# S0-energy-meter-v1_1.net
KiCad netlist of a schematic drawn in EAGLE
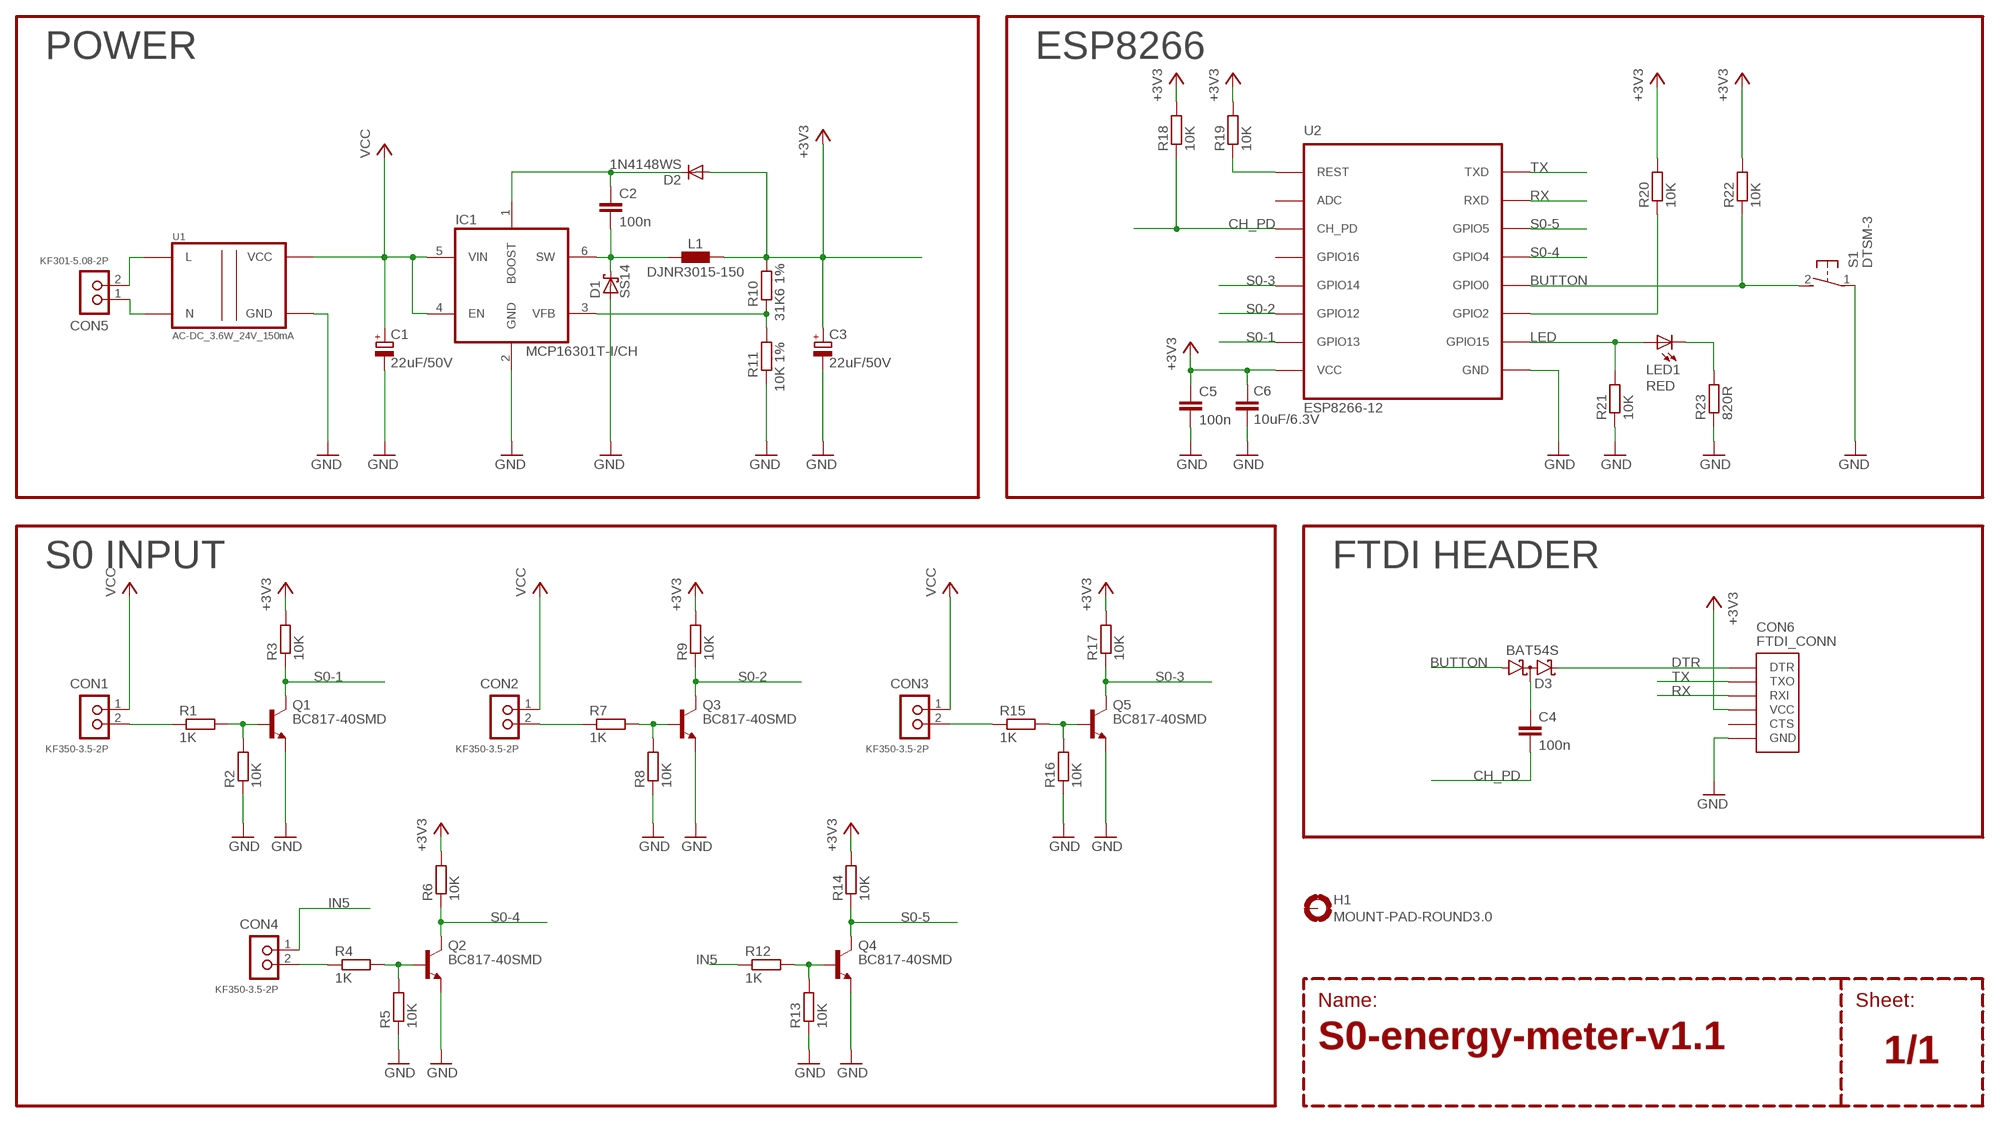
[diagram p0: schematic, sheet 1]

(export (version "E")
  (design (tool "Eeschema 10.0.6"))
  (components
    (comp (ref "C1")
      (value "22uF/50V")
      (footprint "eagle-import:PANASONIC_C")
      (libsource (lib "eagle-import") (part "CPOL-EUC"))
    )
    (comp (ref "C2")
      (value "100n")
      (footprint "eagle-import:C0805")
      (libsource (lib "eagle-import") (part "rcl_334_C-EUC0805"))
    )
    (comp (ref "C3")
      (value "22uF/50V")
      (footprint "eagle-import:PANASONIC_C")
      (libsource (lib "eagle-import") (part "CPOL-EUC"))
    )
    (comp (ref "C4")
      (value "100n")
      (footprint "eagle-import:C0805")
      (libsource (lib "eagle-import") (part "C-EUC0805"))
    )
    (comp (ref "C5")
      (value "100n")
      (footprint "eagle-import:C0805")
      (libsource (lib "eagle-import") (part "rcl_334_C-EUC0805"))
    )
    (comp (ref "C6")
      (value "10uF/6.3V")
      (footprint "eagle-import:C0805")
      (libsource (lib "eagle-import") (part "rcl_334_C-EUC0805"))
    )
    (comp (ref "CON1")
      (value "KF350-3.5-2P")
      (footprint "eagle-import:KF350-3.50-2P")
      (libsource (lib "eagle-import") (part "KF350-3.5-2P"))
    )
    (comp (ref "CON2")
      (value "KF350-3.5-2P")
      (footprint "eagle-import:KF350-3.50-2P")
      (libsource (lib "eagle-import") (part "KF350-3.5-2P"))
    )
    (comp (ref "CON3")
      (value "KF350-3.5-2P")
      (footprint "eagle-import:KF350-3.50-2P")
      (libsource (lib "eagle-import") (part "KF350-3.5-2P"))
    )
    (comp (ref "CON4")
      (value "KF350-3.5-2P")
      (footprint "eagle-import:KF350-3.50-2P")
      (libsource (lib "eagle-import") (part "KF350-3.5-2P"))
    )
    (comp (ref "CON5")
      (value "KF301-5.08-2P")
      (footprint "eagle-import:KF301-5.08-2P")
      (libsource (lib "eagle-import") (part "KF301-?-2P5.08"))
    )
    (comp (ref "CON6")
      (value "FTDI_CONN")
      (footprint "eagle-import:FTDI")
      (libsource (lib "eagle-import") (part "FTDI_CONN"))
    )
    (comp (ref "D1")
      (value "SS14")
      (footprint "eagle-import:DO214AC")
      (libsource (lib "eagle-import") (part "SS?14"))
    )
    (comp (ref "D2")
      (value "1N4148WS")
      (footprint "eagle-import:SOD323")
      (libsource (lib "eagle-import") (part "1N4148WS"))
    )
    (comp (ref "D3")
      (value "BAT54S")
      (footprint "eagle-import:SOT23")
      (libsource (lib "eagle-import") (part "BAT54S"))
    )
    (comp (ref "H1")
      (value "MOUNT-PAD-ROUND3.0")
      (footprint "eagle-import:3,0-PAD")
      (libsource (lib "eagle-import") (part "MOUNT-PAD-ROUND3.0"))
    )
    (comp (ref "IC1")
      (value "MCP16301T-I/CH")
      (footprint "eagle-import:SOT23-6")
      (libsource (lib "eagle-import") (part "MCP16301T-I/?CH"))
    )
    (comp (ref "L1")
      (value "DJNR3015-150")
      (footprint "eagle-import:L3015")
      (libsource (lib "eagle-import") (part "DJNR?-3015150"))
    )
    (comp (ref "LED1")
      (value "RED")
      (footprint "eagle-import:LED0805")
      (libsource (lib "eagle-import") (part "LED0805"))
    )
    (comp (ref "Q1")
      (value "BC817-40SMD")
      (footprint "eagle-import:SOT23-BEC")
      (libsource (lib "eagle-import") (part "BC817SMD-40"))
    )
    (comp (ref "Q2")
      (value "BC817-40SMD")
      (footprint "eagle-import:SOT23-BEC")
      (libsource (lib "eagle-import") (part "BC817SMD-40"))
    )
    (comp (ref "Q3")
      (value "BC817-40SMD")
      (footprint "eagle-import:SOT23-BEC")
      (libsource (lib "eagle-import") (part "BC817SMD-40"))
    )
    (comp (ref "Q4")
      (value "BC817-40SMD")
      (footprint "eagle-import:SOT23-BEC")
      (libsource (lib "eagle-import") (part "BC817SMD-40"))
    )
    (comp (ref "Q5")
      (value "BC817-40SMD")
      (footprint "eagle-import:SOT23-BEC")
      (libsource (lib "eagle-import") (part "BC817SMD-40"))
    )
    (comp (ref "R1")
      (value "1K")
      (footprint "eagle-import:R0805")
      (libsource (lib "eagle-import") (part "R-EU_R0805"))
    )
    (comp (ref "R2")
      (value "10K")
      (footprint "eagle-import:R0805")
      (libsource (lib "eagle-import") (part "R-EU_R0805"))
    )
    (comp (ref "R3")
      (value "10K")
      (footprint "eagle-import:R0805")
      (libsource (lib "eagle-import") (part "R-EU_R0805"))
    )
    (comp (ref "R4")
      (value "1K")
      (footprint "eagle-import:R0805")
      (libsource (lib "eagle-import") (part "R-EU_R0805"))
    )
    (comp (ref "R5")
      (value "10K")
      (footprint "eagle-import:R0805")
      (libsource (lib "eagle-import") (part "R-EU_R0805"))
    )
    (comp (ref "R6")
      (value "10K")
      (footprint "eagle-import:R0805")
      (libsource (lib "eagle-import") (part "R-EU_R0805"))
    )
    (comp (ref "R7")
      (value "1K")
      (footprint "eagle-import:R0805")
      (libsource (lib "eagle-import") (part "R-EU_R0805"))
    )
    (comp (ref "R8")
      (value "10K")
      (footprint "eagle-import:R0805")
      (libsource (lib "eagle-import") (part "R-EU_R0805"))
    )
    (comp (ref "R9")
      (value "10K")
      (footprint "eagle-import:R0805")
      (libsource (lib "eagle-import") (part "R-EU_R0805"))
    )
    (comp (ref "R10")
      (value "31K6 1%")
      (footprint "eagle-import:R0805")
      (libsource (lib "eagle-import") (part "R-EU_R0805"))
    )
    (comp (ref "R11")
      (value "10K 1%")
      (footprint "eagle-import:R0805")
      (libsource (lib "eagle-import") (part "R-EU_R0805"))
    )
    (comp (ref "R12")
      (value "1K")
      (footprint "eagle-import:R0805")
      (libsource (lib "eagle-import") (part "R-EU_R0805"))
    )
    (comp (ref "R13")
      (value "10K")
      (footprint "eagle-import:R0805")
      (libsource (lib "eagle-import") (part "R-EU_R0805"))
    )
    (comp (ref "R14")
      (value "10K")
      (footprint "eagle-import:R0805")
      (libsource (lib "eagle-import") (part "R-EU_R0805"))
    )
    (comp (ref "R15")
      (value "1K")
      (footprint "eagle-import:R0805")
      (libsource (lib "eagle-import") (part "R-EU_R0805"))
    )
    (comp (ref "R16")
      (value "10K")
      (footprint "eagle-import:R0805")
      (libsource (lib "eagle-import") (part "R-EU_R0805"))
    )
    (comp (ref "R17")
      (value "10K")
      (footprint "eagle-import:R0805")
      (libsource (lib "eagle-import") (part "R-EU_R0805"))
    )
    (comp (ref "R18")
      (value "10K")
      (footprint "eagle-import:R0805")
      (libsource (lib "eagle-import") (part "R-EU_R0805"))
    )
    (comp (ref "R19")
      (value "10K")
      (footprint "eagle-import:R0805")
      (libsource (lib "eagle-import") (part "R-EU_R0805"))
    )
    (comp (ref "R20")
      (value "10K")
      (footprint "eagle-import:R0805")
      (libsource (lib "eagle-import") (part "R-EU_R0805"))
    )
    (comp (ref "R21")
      (value "10K")
      (footprint "eagle-import:R0805")
      (libsource (lib "eagle-import") (part "R-EU_R0805"))
    )
    (comp (ref "R22")
      (value "10K")
      (footprint "eagle-import:R0805")
      (libsource (lib "eagle-import") (part "R-EU_R0805"))
    )
    (comp (ref "R23")
      (value "820R")
      (footprint "eagle-import:R0805")
      (libsource (lib "eagle-import") (part "R-EU_R0805"))
    )
    (comp (ref "S1")
      (value "DTSM-3")
      (footprint "eagle-import:DTSM-3")
      (libsource (lib "eagle-import") (part "DTSM-3"))
    )
    (comp (ref "U1")
      (value "AC-DC_3.6W_24V_150mA")
      (footprint "eagle-import:AC_DC_24V_150MA")
      (libsource (lib "eagle-import") (part "AC-DC_?3.6W"))
    )
    (comp (ref "U2")
      (value "ESP8266-12")
      (footprint "eagle-import:ESP-12")
      (libsource (lib "eagle-import") (part "ESP8266-12"))
    )
  )
  (nets
    (net (code "1") (name "+3V3") (class "Default")
      (node (ref "C3") (pin "+") (pinfunction "+_+") (pintype "passive"))
      (node (ref "C5") (pin "1") (pinfunction "1_1") (pintype "passive"))
      (node (ref "C6") (pin "1") (pinfunction "1_1") (pintype "passive"))
      (node (ref "CON6") (pin "P$4") (pinfunction "VCC_P$4") (pintype "bidirectional"))
      (node (ref "D2") (pin "A") (pinfunction "A_A") (pintype "passive"))
      (node (ref "L1") (pin "1") (pinfunction "1_1") (pintype "passive"))
      (node (ref "R10") (pin "2") (pinfunction "2_2") (pintype "passive"))
      (node (ref "R14") (pin "2") (pinfunction "2_2") (pintype "passive"))
      (node (ref "R17") (pin "2") (pinfunction "2_2") (pintype "passive"))
      (node (ref "R18") (pin "2") (pinfunction "2_2") (pintype "passive"))
      (node (ref "R19") (pin "2") (pinfunction "2_2") (pintype "passive"))
      (node (ref "R20") (pin "2") (pinfunction "2_2") (pintype "passive"))
      (node (ref "R22") (pin "2") (pinfunction "2_2") (pintype "passive"))
      (node (ref "R3") (pin "2") (pinfunction "2_2") (pintype "passive"))
      (node (ref "R6") (pin "2") (pinfunction "2_2") (pintype "passive"))
      (node (ref "R9") (pin "2") (pinfunction "2_2") (pintype "passive"))
      (node (ref "U2") (pin "VCC") (pinfunction "VCC_VCC") (pintype "power_in"))
    )
    (net (code "2") (name "/BUTTON") (class "Default")
      (node (ref "D3") (pin "1") (pinfunction "A1_1") (pintype "passive"))
      (node (ref "R22") (pin "1") (pinfunction "1_1") (pintype "passive"))
      (node (ref "S1") (pin "2") (pinfunction "2_2") (pintype "passive"))
      (node (ref "U2") (pin "GPIO0") (pinfunction "GPIO0_GPIO0") (pintype "bidirectional"))
    )
    (net (code "3") (name "/CH_PD") (class "Default")
      (node (ref "C4") (pin "2") (pinfunction "2_2") (pintype "passive"))
      (node (ref "R18") (pin "1") (pinfunction "1_1") (pintype "passive"))
      (node (ref "U2") (pin "CH_PD") (pinfunction "CH_PD_CH_PD") (pintype "power_in"))
    )
    (net (code "4") (name "/DTR") (class "Default")
      (node (ref "CON6") (pin "P$1") (pinfunction "DTR_P$1") (pintype "bidirectional"))
      (node (ref "D3") (pin "2") (pinfunction "C2_2") (pintype "passive"))
    )
    (net (code "5") (name "/IN5") (class "Default")
      (node (ref "CON4") (pin "1") (pinfunction "1_1") (pintype "passive"))
      (node (ref "R12") (pin "1") (pinfunction "1_1") (pintype "passive"))
    )
    (net (code "6") (name "/LED") (class "Default")
      (node (ref "LED1") (pin "A") (pinfunction "A_A") (pintype "passive"))
      (node (ref "R21") (pin "2") (pinfunction "2_2") (pintype "passive"))
      (node (ref "U2") (pin "GPIO15") (pinfunction "GPIO15_GPIO15") (pintype "bidirectional"))
    )
    (net (code "7") (name "/RX") (class "Default")
      (node (ref "CON6") (pin "P$3") (pinfunction "RXI_P$3") (pintype "bidirectional"))
      (node (ref "U2") (pin "RXD") (pinfunction "RXD_RXD") (pintype "bidirectional"))
    )
    (net (code "8") (name "/S0-1") (class "Default")
      (node (ref "Q1") (pin "C") (pinfunction "C_C") (pintype "passive"))
      (node (ref "R3") (pin "1") (pinfunction "1_1") (pintype "passive"))
      (node (ref "U2") (pin "GPIO13") (pinfunction "GPIO13_GPIO13") (pintype "bidirectional"))
    )
    (net (code "9") (name "/S0-2") (class "Default")
      (node (ref "Q3") (pin "C") (pinfunction "C_C") (pintype "passive"))
      (node (ref "R9") (pin "1") (pinfunction "1_1") (pintype "passive"))
      (node (ref "U2") (pin "GPIO12") (pinfunction "GPIO12_GPIO12") (pintype "bidirectional"))
    )
    (net (code "10") (name "/S0-3") (class "Default")
      (node (ref "Q5") (pin "C") (pinfunction "C_C") (pintype "passive"))
      (node (ref "R17") (pin "1") (pinfunction "1_1") (pintype "passive"))
      (node (ref "U2") (pin "GPIO14") (pinfunction "GPIO14_GPIO14") (pintype "bidirectional"))
    )
    (net (code "11") (name "/S0-4") (class "Default")
      (node (ref "Q2") (pin "C") (pinfunction "C_C") (pintype "passive"))
      (node (ref "R6") (pin "1") (pinfunction "1_1") (pintype "passive"))
      (node (ref "U2") (pin "GPIO4") (pinfunction "GPIO4_GPIO4") (pintype "bidirectional"))
    )
    (net (code "12") (name "/S0-5") (class "Default")
      (node (ref "Q4") (pin "C") (pinfunction "C_C") (pintype "passive"))
      (node (ref "R14") (pin "1") (pinfunction "1_1") (pintype "passive"))
      (node (ref "U2") (pin "GPIO5") (pinfunction "GPIO5_GPIO5") (pintype "bidirectional"))
    )
    (net (code "13") (name "/TX") (class "Default")
      (node (ref "CON6") (pin "P$2") (pinfunction "TXO_P$2") (pintype "bidirectional"))
      (node (ref "U2") (pin "TXD") (pinfunction "TXD_TXD") (pintype "bidirectional"))
    )
    (net (code "14") (name "GND") (class "Default")
      (node (ref "C1") (pin "-") (pinfunction "-_-") (pintype "passive"))
      (node (ref "C3") (pin "-") (pinfunction "-_-") (pintype "passive"))
      (node (ref "C5") (pin "2") (pinfunction "2_2") (pintype "passive"))
      (node (ref "C6") (pin "2") (pinfunction "2_2") (pintype "passive"))
      (node (ref "CON6") (pin "P$6") (pinfunction "GND_P$6") (pintype "bidirectional"))
      (node (ref "D1") (pin "A") (pinfunction "A_A") (pintype "passive"))
      (node (ref "IC1") (pin "2") (pinfunction "GND_2") (pintype "power_in"))
      (node (ref "Q1") (pin "E") (pinfunction "E_E") (pintype "passive"))
      (node (ref "Q2") (pin "E") (pinfunction "E_E") (pintype "passive"))
      (node (ref "Q3") (pin "E") (pinfunction "E_E") (pintype "passive"))
      (node (ref "Q4") (pin "E") (pinfunction "E_E") (pintype "passive"))
      (node (ref "Q5") (pin "E") (pinfunction "E_E") (pintype "passive"))
      (node (ref "R11") (pin "1") (pinfunction "1_1") (pintype "passive"))
      (node (ref "R13") (pin "1") (pinfunction "1_1") (pintype "passive"))
      (node (ref "R16") (pin "1") (pinfunction "1_1") (pintype "passive"))
      (node (ref "R2") (pin "1") (pinfunction "1_1") (pintype "passive"))
      (node (ref "R21") (pin "1") (pinfunction "1_1") (pintype "passive"))
      (node (ref "R23") (pin "1") (pinfunction "1_1") (pintype "passive"))
      (node (ref "R5") (pin "1") (pinfunction "1_1") (pintype "passive"))
      (node (ref "R8") (pin "1") (pinfunction "1_1") (pintype "passive"))
      (node (ref "S1") (pin "1") (pinfunction "1_1") (pintype "passive"))
      (node (ref "U1") (pin "GND") (pinfunction "GND_GND") (pintype "power_in"))
      (node (ref "U2") (pin "GND") (pinfunction "GND_GND") (pintype "power_in"))
    )
    (net (code "15") (name "Net-(CON1-Pad2)") (class "Default")
      (node (ref "CON1") (pin "2") (pinfunction "2_2") (pintype "passive"))
      (node (ref "R1") (pin "1") (pinfunction "1_1") (pintype "passive"))
    )
    (net (code "16") (name "Net-(CON2-Pad2)") (class "Default")
      (node (ref "CON2") (pin "2") (pinfunction "2_2") (pintype "passive"))
      (node (ref "R7") (pin "1") (pinfunction "1_1") (pintype "passive"))
    )
    (net (code "17") (name "Net-(CON3-Pad2)") (class "Default")
      (node (ref "CON3") (pin "2") (pinfunction "2_2") (pintype "passive"))
      (node (ref "R15") (pin "1") (pinfunction "1_1") (pintype "passive"))
    )
    (net (code "18") (name "Net-(CON4-Pad2)") (class "Default")
      (node (ref "CON4") (pin "2") (pinfunction "2_2") (pintype "passive"))
      (node (ref "R4") (pin "1") (pinfunction "1_1") (pintype "passive"))
    )
    (net (code "19") (name "Net-(CON5-Pad1)") (class "Default")
      (node (ref "CON5") (pin "1") (pinfunction "1_1") (pintype "passive"))
      (node (ref "U1") (pin "N") (pinfunction "N_N") (pintype "power_in"))
    )
    (net (code "20") (name "Net-(CON5-Pad2)") (class "Default")
      (node (ref "CON5") (pin "2") (pinfunction "2_2") (pintype "passive"))
      (node (ref "U1") (pin "L") (pinfunction "L_L") (pintype "power_in"))
    )
    (net (code "21") (name "Net-(D3-C1A2)") (class "Default")
      (node (ref "C4") (pin "1") (pinfunction "1_1") (pintype "passive"))
      (node (ref "D3") (pin "3") (pinfunction "C1A2_3") (pintype "passive"))
    )
    (net (code "22") (name "Net-(IC1-BOOST)") (class "Default")
      (node (ref "C2") (pin "1") (pinfunction "1_1") (pintype "passive"))
      (node (ref "D2") (pin "C") (pinfunction "C_C") (pintype "passive"))
      (node (ref "IC1") (pin "1") (pinfunction "BOOST_1") (pintype "passive"))
    )
    (net (code "23") (name "Net-(IC1-SW)") (class "Default")
      (node (ref "C2") (pin "2") (pinfunction "2_2") (pintype "passive"))
      (node (ref "D1") (pin "C") (pinfunction "C_C") (pintype "passive"))
      (node (ref "IC1") (pin "6") (pinfunction "SW_6") (pintype "output"))
      (node (ref "L1") (pin "2") (pinfunction "2_2") (pintype "passive"))
    )
    (net (code "24") (name "Net-(IC1-VFB)") (class "Default")
      (node (ref "IC1") (pin "3") (pinfunction "VFB_3") (pintype "input"))
      (node (ref "R10") (pin "1") (pinfunction "1_1") (pintype "passive"))
      (node (ref "R11") (pin "2") (pinfunction "2_2") (pintype "passive"))
    )
    (net (code "25") (name "Net-(LED1-PadC)") (class "Default")
      (node (ref "LED1") (pin "C") (pinfunction "C_C") (pintype "passive"))
      (node (ref "R23") (pin "2") (pinfunction "2_2") (pintype "passive"))
    )
    (net (code "26") (name "Net-(Q1-PadB)") (class "Default")
      (node (ref "Q1") (pin "B") (pinfunction "B_B") (pintype "passive"))
      (node (ref "R1") (pin "2") (pinfunction "2_2") (pintype "passive"))
      (node (ref "R2") (pin "2") (pinfunction "2_2") (pintype "passive"))
    )
    (net (code "27") (name "Net-(Q2-PadB)") (class "Default")
      (node (ref "Q2") (pin "B") (pinfunction "B_B") (pintype "passive"))
      (node (ref "R4") (pin "2") (pinfunction "2_2") (pintype "passive"))
      (node (ref "R5") (pin "2") (pinfunction "2_2") (pintype "passive"))
    )
    (net (code "28") (name "Net-(Q3-PadB)") (class "Default")
      (node (ref "Q3") (pin "B") (pinfunction "B_B") (pintype "passive"))
      (node (ref "R7") (pin "2") (pinfunction "2_2") (pintype "passive"))
      (node (ref "R8") (pin "2") (pinfunction "2_2") (pintype "passive"))
    )
    (net (code "29") (name "Net-(Q4-PadB)") (class "Default")
      (node (ref "Q4") (pin "B") (pinfunction "B_B") (pintype "passive"))
      (node (ref "R12") (pin "2") (pinfunction "2_2") (pintype "passive"))
      (node (ref "R13") (pin "2") (pinfunction "2_2") (pintype "passive"))
    )
    (net (code "30") (name "Net-(Q5-PadB)") (class "Default")
      (node (ref "Q5") (pin "B") (pinfunction "B_B") (pintype "passive"))
      (node (ref "R15") (pin "2") (pinfunction "2_2") (pintype "passive"))
      (node (ref "R16") (pin "2") (pinfunction "2_2") (pintype "passive"))
    )
    (net (code "31") (name "Net-(R19-Pad1)") (class "Default")
      (node (ref "R19") (pin "1") (pinfunction "1_1") (pintype "passive"))
      (node (ref "U2") (pin "REST") (pinfunction "REST_REST") (pintype "bidirectional"))
    )
    (net (code "32") (name "Net-(R20-Pad1)") (class "Default")
      (node (ref "R20") (pin "1") (pinfunction "1_1") (pintype "passive"))
      (node (ref "U2") (pin "GPIO2") (pinfunction "GPIO2_GPIO2") (pintype "bidirectional"))
    )
    (net (code "33") (name "VCC") (class "Default")
      (node (ref "C1") (pin "+") (pinfunction "+_+") (pintype "passive"))
      (node (ref "CON1") (pin "1") (pinfunction "1_1") (pintype "passive"))
      (node (ref "CON2") (pin "1") (pinfunction "1_1") (pintype "passive"))
      (node (ref "CON3") (pin "1") (pinfunction "1_1") (pintype "passive"))
      (node (ref "IC1") (pin "4") (pinfunction "EN_4") (pintype "input"))
      (node (ref "IC1") (pin "5") (pinfunction "VIN_5") (pintype "power_in"))
      (node (ref "U1") (pin "VCC") (pinfunction "VCC_VCC") (pintype "power_in"))
    )
    (net (code "34") (name "unconnected-(CON6-CTS-PadP$5)") (class "Default")
      (node (ref "CON6") (pin "P$5") (pinfunction "CTS_P$5") (pintype "bidirectional"))
    )
    (net (code "35") (name "unconnected-(H1-MOUNT-PadB3,0)") (class "Default")
      (node (ref "H1") (pin "B3,0") (pinfunction "MOUNT_B3,0") (pintype "passive"))
    )
    (net (code "36") (name "unconnected-(U2-PadADC)") (class "Default")
      (node (ref "U2") (pin "ADC") (pinfunction "ADC_ADC") (pintype "bidirectional"))
    )
    (net (code "37") (name "unconnected-(U2-PadGPIO16)") (class "Default")
      (node (ref "U2") (pin "GPIO16") (pinfunction "GPIO16_GPIO16") (pintype "bidirectional"))
    )
  )
)
